# SCH_pave_2026-02-10.net
KiCad netlist of a schematic drawn in EasyEDA
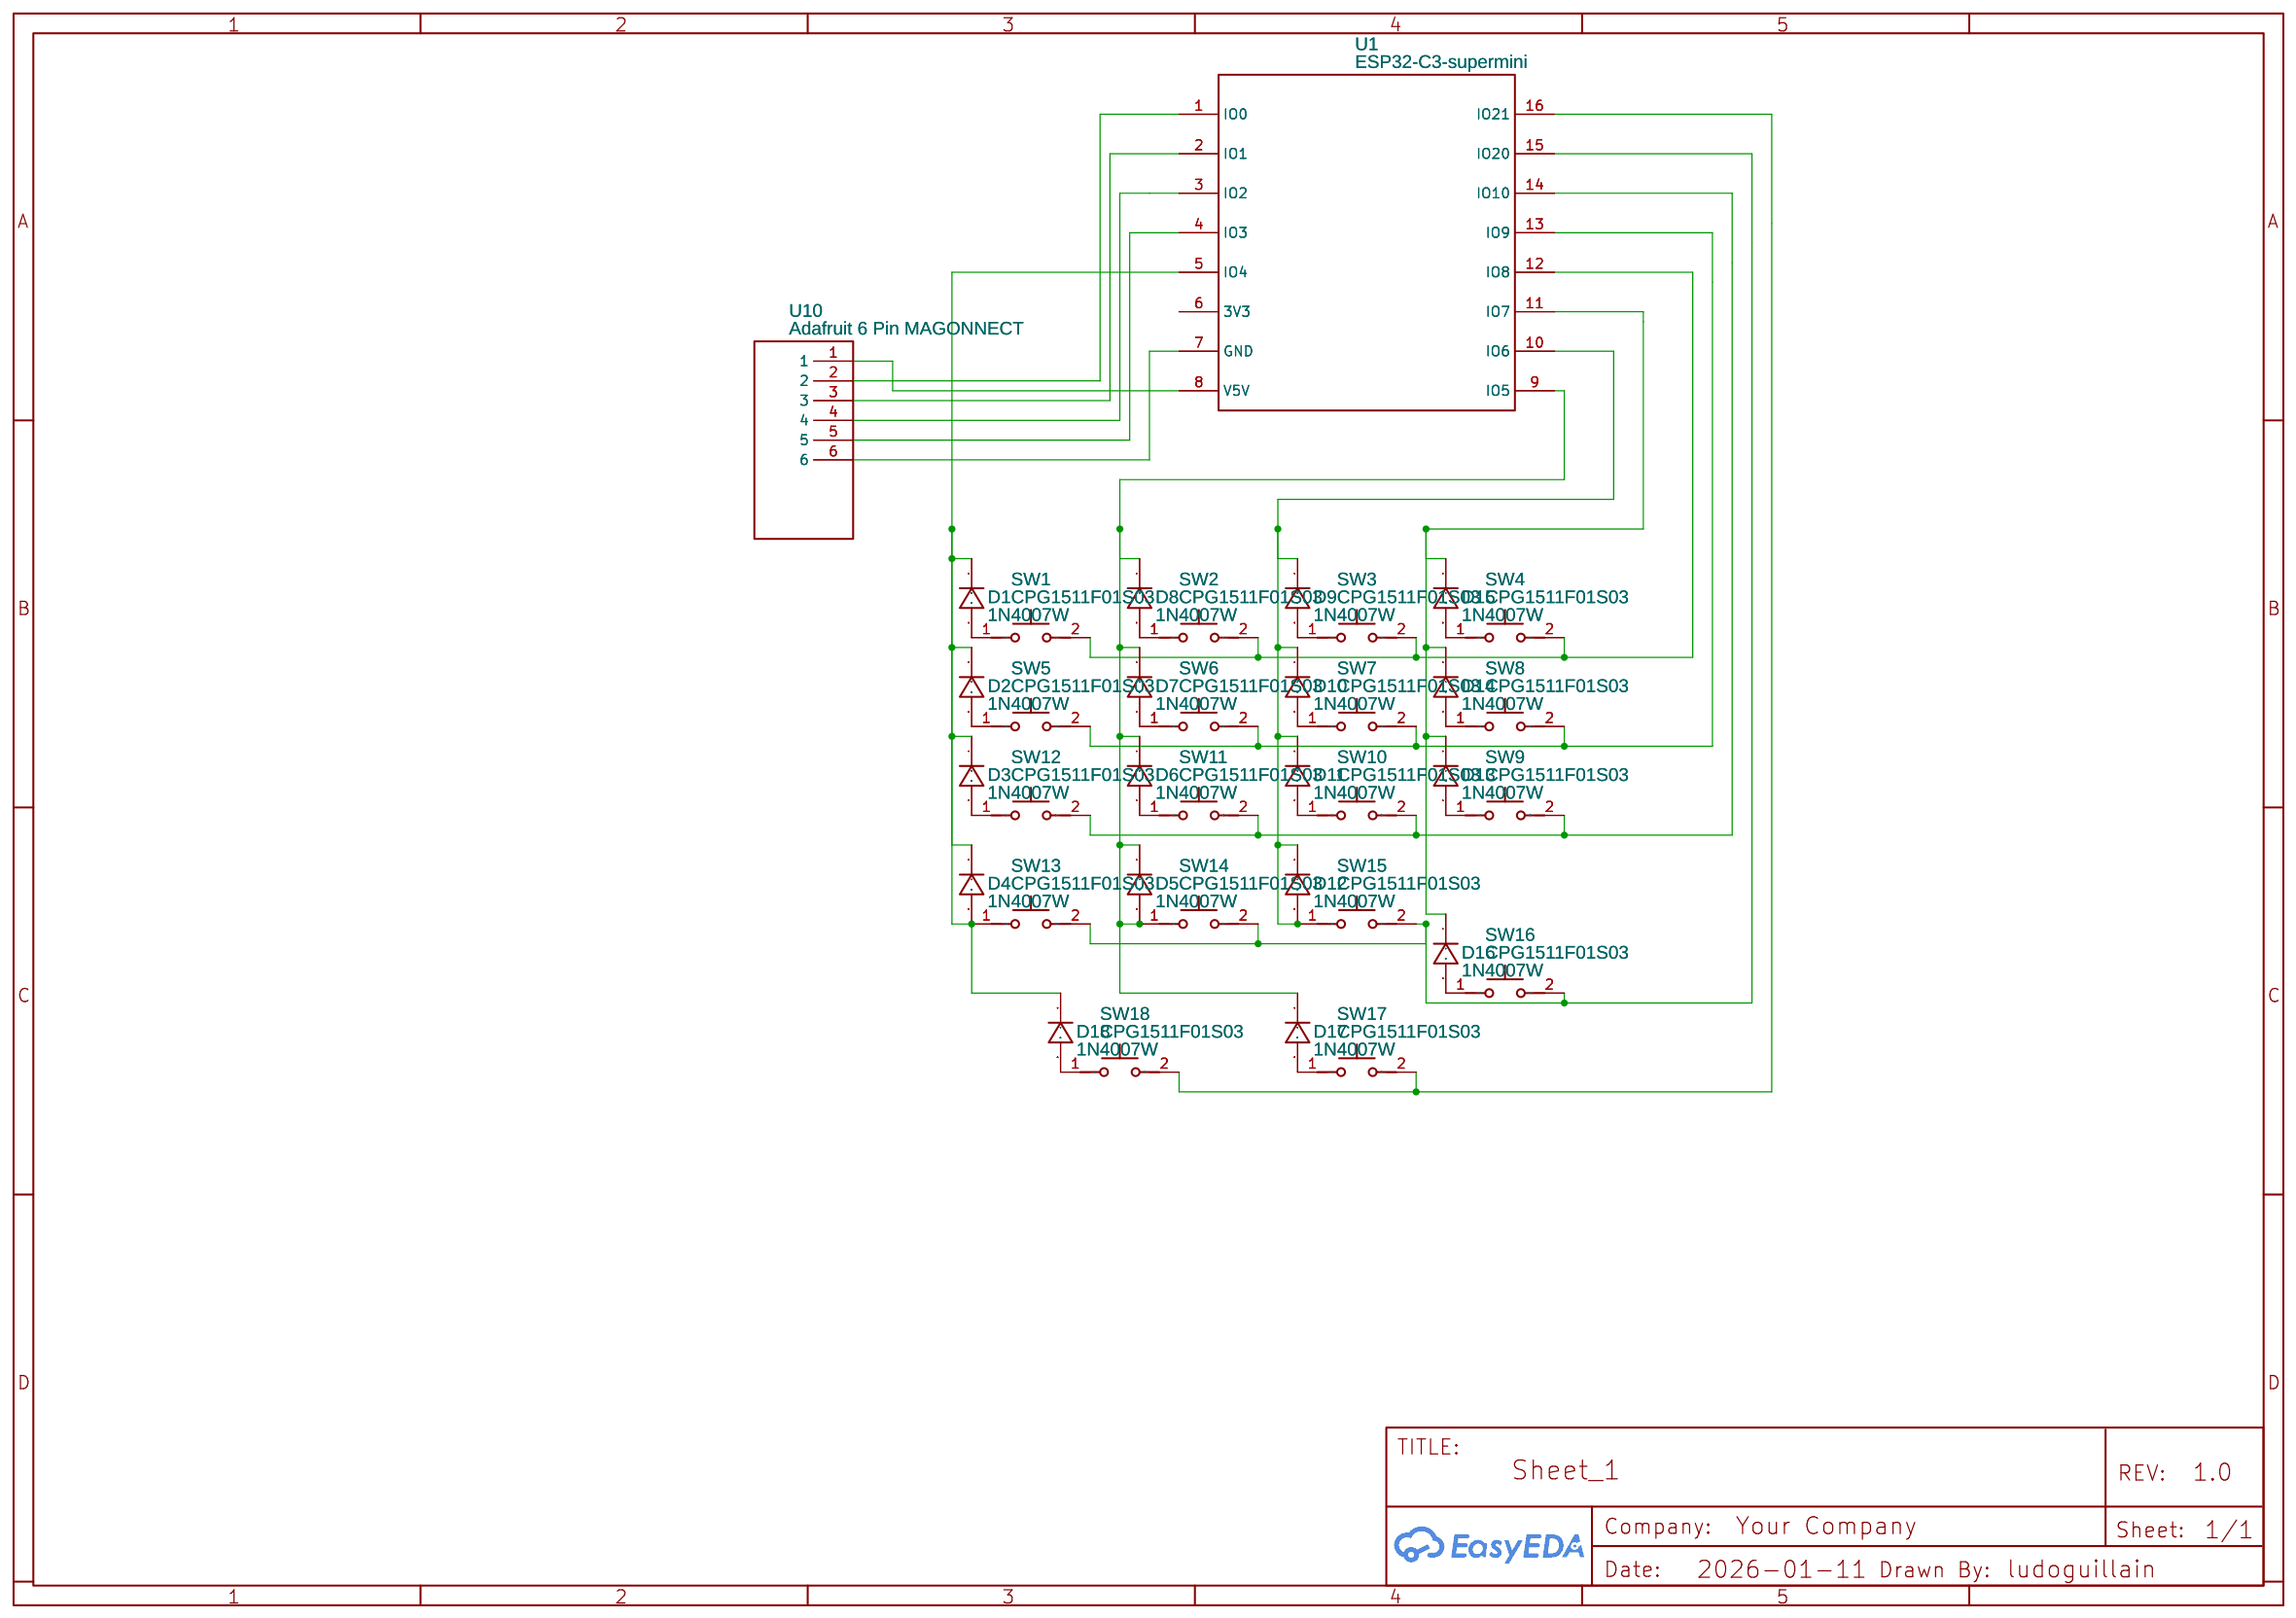
[diagram p0: schematic sheet]

(export (version "E")
  (design (tool "Eeschema 10.0.6"))
  (components
    (comp (ref "D1")
      (value "1N4007W")
      (fields (field (name "Manufacturer") "BLUE ROCKET"))
      (libsource (lib "") (part "1N4007W"))
    )
    (comp (ref "D2")
      (value "1N4007W")
      (fields (field (name "Manufacturer") "BLUE ROCKET"))
      (libsource (lib "") (part "1N4007W"))
    )
    (comp (ref "D3")
      (value "1N4007W")
      (fields (field (name "Manufacturer") "BLUE ROCKET"))
      (libsource (lib "") (part "1N4007W"))
    )
    (comp (ref "D4")
      (value "1N4007W")
      (fields (field (name "Manufacturer") "BLUE ROCKET"))
      (libsource (lib "") (part "1N4007W"))
    )
    (comp (ref "D5")
      (value "1N4007W")
      (fields (field (name "Manufacturer") "BLUE ROCKET"))
      (libsource (lib "") (part "1N4007W"))
    )
    (comp (ref "D6")
      (value "1N4007W")
      (fields (field (name "Manufacturer") "BLUE ROCKET"))
      (libsource (lib "") (part "1N4007W"))
    )
    (comp (ref "D7")
      (value "1N4007W")
      (fields (field (name "Manufacturer") "BLUE ROCKET"))
      (libsource (lib "") (part "1N4007W"))
    )
    (comp (ref "D8")
      (value "1N4007W")
      (fields (field (name "Manufacturer") "BLUE ROCKET"))
      (libsource (lib "") (part "1N4007W"))
    )
    (comp (ref "D9")
      (value "1N4007W")
      (fields (field (name "Manufacturer") "BLUE ROCKET"))
      (libsource (lib "") (part "1N4007W"))
    )
    (comp (ref "D10")
      (value "1N4007W")
      (fields (field (name "Manufacturer") "BLUE ROCKET"))
      (libsource (lib "") (part "1N4007W"))
    )
    (comp (ref "D11")
      (value "1N4007W")
      (fields (field (name "Manufacturer") "BLUE ROCKET"))
      (libsource (lib "") (part "1N4007W"))
    )
    (comp (ref "D12")
      (value "1N4007W")
      (fields (field (name "Manufacturer") "BLUE ROCKET"))
      (libsource (lib "") (part "1N4007W"))
    )
    (comp (ref "D13")
      (value "1N4007W")
      (fields (field (name "Manufacturer") "BLUE ROCKET"))
      (libsource (lib "") (part "1N4007W"))
    )
    (comp (ref "D14")
      (value "1N4007W")
      (fields (field (name "Manufacturer") "BLUE ROCKET"))
      (libsource (lib "") (part "1N4007W"))
    )
    (comp (ref "D15")
      (value "1N4007W")
      (fields (field (name "Manufacturer") "BLUE ROCKET"))
      (libsource (lib "") (part "1N4007W"))
    )
    (comp (ref "D16")
      (value "1N4007W")
      (fields (field (name "Manufacturer") "BLUE ROCKET"))
      (libsource (lib "") (part "1N4007W"))
    )
    (comp (ref "D17")
      (value "1N4007W")
      (fields (field (name "Manufacturer") "BLUE ROCKET"))
      (libsource (lib "") (part "1N4007W"))
    )
    (comp (ref "D18")
      (value "1N4007W")
      (fields (field (name "Manufacturer") "BLUE ROCKET"))
      (libsource (lib "") (part "1N4007W"))
    )
    (comp (ref "SW1")
      (value "CPG1511F01S03")
      (fields (field (name "Manufacturer") "Kailh(凯华)"))
      (libsource (lib "") (part "CPG1511F01S03"))
    )
    (comp (ref "SW2")
      (value "CPG1511F01S03")
      (fields (field (name "Manufacturer") "Kailh(凯华)"))
      (libsource (lib "") (part "CPG1511F01S03"))
    )
    (comp (ref "SW3")
      (value "CPG1511F01S03")
      (fields (field (name "Manufacturer") "Kailh(凯华)"))
      (libsource (lib "") (part "CPG1511F01S03"))
    )
    (comp (ref "SW4")
      (value "CPG1511F01S03")
      (fields (field (name "Manufacturer") "Kailh(凯华)"))
      (libsource (lib "") (part "CPG1511F01S03"))
    )
    (comp (ref "SW5")
      (value "CPG1511F01S03")
      (fields (field (name "Manufacturer") "Kailh(凯华)"))
      (libsource (lib "") (part "CPG1511F01S03"))
    )
    (comp (ref "SW6")
      (value "CPG1511F01S03")
      (fields (field (name "Manufacturer") "Kailh(凯华)"))
      (libsource (lib "") (part "CPG1511F01S03"))
    )
    (comp (ref "SW7")
      (value "CPG1511F01S03")
      (fields (field (name "Manufacturer") "Kailh(凯华)"))
      (libsource (lib "") (part "CPG1511F01S03"))
    )
    (comp (ref "SW8")
      (value "CPG1511F01S03")
      (fields (field (name "Manufacturer") "Kailh(凯华)"))
      (libsource (lib "") (part "CPG1511F01S03"))
    )
    (comp (ref "SW9")
      (value "CPG1511F01S03")
      (fields (field (name "Manufacturer") "Kailh(凯华)"))
      (libsource (lib "") (part "CPG1511F01S03"))
    )
    (comp (ref "SW10")
      (value "CPG1511F01S03")
      (fields (field (name "Manufacturer") "Kailh(凯华)"))
      (libsource (lib "") (part "CPG1511F01S03"))
    )
    (comp (ref "SW11")
      (value "CPG1511F01S03")
      (fields (field (name "Manufacturer") "Kailh(凯华)"))
      (libsource (lib "") (part "CPG1511F01S03"))
    )
    (comp (ref "SW12")
      (value "CPG1511F01S03")
      (fields (field (name "Manufacturer") "Kailh(凯华)"))
      (libsource (lib "") (part "CPG1511F01S03"))
    )
    (comp (ref "SW13")
      (value "CPG1511F01S03")
      (fields (field (name "Manufacturer") "Kailh(凯华)"))
      (libsource (lib "") (part "CPG1511F01S03"))
    )
    (comp (ref "SW14")
      (value "CPG1511F01S03")
      (fields (field (name "Manufacturer") "Kailh(凯华)"))
      (libsource (lib "") (part "CPG1511F01S03"))
    )
    (comp (ref "SW15")
      (value "CPG1511F01S03")
      (fields (field (name "Manufacturer") "Kailh(凯华)"))
      (libsource (lib "") (part "CPG1511F01S03"))
    )
    (comp (ref "SW16")
      (value "CPG1511F01S03")
      (fields (field (name "Manufacturer") "Kailh(凯华)"))
      (libsource (lib "") (part "CPG1511F01S03"))
    )
    (comp (ref "SW17")
      (value "CPG1511F01S03")
      (fields (field (name "Manufacturer") "Kailh(凯华)"))
      (libsource (lib "") (part "CPG1511F01S03"))
    )
    (comp (ref "SW18")
      (value "CPG1511F01S03")
      (fields (field (name "Manufacturer") "Kailh(凯华)"))
      (libsource (lib "") (part "CPG1511F01S03"))
    )
    (comp (ref "U1") (value "ESP32-C3-supermini") (libsource (lib "") (part "ESP32-C3-supermini")))
    (comp (ref "U10")
      (value "Adafruit 6 Pin MAGONNECT")
      (libsource (lib "") (part "Adafruit 6 Pin MAGONNECT"))
    )
  )
  (nets
    (net (code "1") (name "Net-(D1-Pad2)") (class "Default")
      (node (ref "D1") (pin "2") (pinfunction "2_2") (pintype "unspecified"))
      (node (ref "SW1") (pin "1") (pinfunction "1_1") (pintype "unspecified"))
    )
    (net (code "2") (name "Net-(D2-Pad2)") (class "Default")
      (node (ref "D2") (pin "2") (pinfunction "2_2") (pintype "unspecified"))
      (node (ref "SW5") (pin "1") (pinfunction "1_1") (pintype "unspecified"))
    )
    (net (code "3") (name "Net-(D3-Pad2)") (class "Default")
      (node (ref "D3") (pin "2") (pinfunction "2_2") (pintype "unspecified"))
      (node (ref "SW12") (pin "1") (pinfunction "1_1") (pintype "unspecified"))
    )
    (net (code "4") (name "Net-(D6-Pad2)") (class "Default")
      (node (ref "D6") (pin "2") (pinfunction "2_2") (pintype "unspecified"))
      (node (ref "SW11") (pin "1") (pinfunction "1_1") (pintype "unspecified"))
    )
    (net (code "5") (name "Net-(D7-Pad2)") (class "Default")
      (node (ref "D7") (pin "2") (pinfunction "2_2") (pintype "unspecified"))
      (node (ref "SW6") (pin "1") (pinfunction "1_1") (pintype "unspecified"))
    )
    (net (code "6") (name "Net-(D8-Pad2)") (class "Default")
      (node (ref "D8") (pin "2") (pinfunction "2_2") (pintype "unspecified"))
      (node (ref "SW2") (pin "1") (pinfunction "1_1") (pintype "unspecified"))
    )
    (net (code "7") (name "Net-(D9-Pad2)") (class "Default")
      (node (ref "D9") (pin "2") (pinfunction "2_2") (pintype "unspecified"))
      (node (ref "SW3") (pin "1") (pinfunction "1_1") (pintype "unspecified"))
    )
    (net (code "8") (name "Net-(D10-Pad2)") (class "Default")
      (node (ref "D10") (pin "2") (pinfunction "2_2") (pintype "unspecified"))
      (node (ref "SW7") (pin "1") (pinfunction "1_1") (pintype "unspecified"))
    )
    (net (code "9") (name "Net-(D11-Pad2)") (class "Default")
      (node (ref "D11") (pin "2") (pinfunction "2_2") (pintype "unspecified"))
      (node (ref "SW10") (pin "1") (pinfunction "1_1") (pintype "unspecified"))
    )
    (net (code "10") (name "Net-(D13-Pad2)") (class "Default")
      (node (ref "D13") (pin "2") (pinfunction "2_2") (pintype "unspecified"))
      (node (ref "SW9") (pin "1") (pinfunction "1_1") (pintype "unspecified"))
    )
    (net (code "11") (name "Net-(D14-Pad2)") (class "Default")
      (node (ref "D14") (pin "2") (pinfunction "2_2") (pintype "unspecified"))
      (node (ref "SW8") (pin "1") (pinfunction "1_1") (pintype "unspecified"))
    )
    (net (code "12") (name "Net-(D15-Pad2)") (class "Default")
      (node (ref "D15") (pin "2") (pinfunction "2_2") (pintype "unspecified"))
      (node (ref "SW4") (pin "1") (pinfunction "1_1") (pintype "unspecified"))
    )
    (net (code "13") (name "Net-(D16-Pad2)") (class "Default")
      (node (ref "D16") (pin "2") (pinfunction "2_2") (pintype "unspecified"))
      (node (ref "SW16") (pin "1") (pinfunction "1_1") (pintype "unspecified"))
    )
    (net (code "14") (name "Net-(D17-Pad2)") (class "Default")
      (node (ref "D17") (pin "2") (pinfunction "2_2") (pintype "unspecified"))
      (node (ref "SW17") (pin "1") (pinfunction "1_1") (pintype "unspecified"))
    )
    (net (code "15") (name "Net-(D18-Pad2)") (class "Default")
      (node (ref "D18") (pin "2") (pinfunction "2_2") (pintype "unspecified"))
      (node (ref "SW18") (pin "1") (pinfunction "1_1") (pintype "unspecified"))
    )
    (net (code "16") (name "Net-(U1-GND)") (class "Default")
      (node (ref "U1") (pin "7") (pinfunction "GND_7") (pintype "unspecified"))
      (node (ref "U10") (pin "6") (pinfunction "6_6") (pintype "unspecified"))
    )
    (net (code "17") (name "Net-(U1-IO0)") (class "Default")
      (node (ref "U1") (pin "1") (pinfunction "IO0_1") (pintype "unspecified"))
      (node (ref "U10") (pin "2") (pinfunction "2_2") (pintype "unspecified"))
    )
    (net (code "18") (name "Net-(U1-IO1)") (class "Default")
      (node (ref "U1") (pin "2") (pinfunction "IO1_2") (pintype "unspecified"))
      (node (ref "U10") (pin "3") (pinfunction "3_3") (pintype "unspecified"))
    )
    (net (code "19") (name "Net-(U1-IO2)") (class "Default")
      (node (ref "U1") (pin "3") (pinfunction "IO2_3") (pintype "unspecified"))
      (node (ref "U10") (pin "4") (pinfunction "4_4") (pintype "unspecified"))
    )
    (net (code "20") (name "Net-(U1-IO3)") (class "Default")
      (node (ref "U1") (pin "4") (pinfunction "IO3_4") (pintype "unspecified"))
      (node (ref "U10") (pin "5") (pinfunction "5_5") (pintype "unspecified"))
    )
    (net (code "21") (name "Net-(U1-IO4)") (class "Default")
      (node (ref "D1") (pin "1") (pinfunction "1_1") (pintype "unspecified"))
      (node (ref "D18") (pin "1") (pinfunction "1_1") (pintype "unspecified"))
      (node (ref "D2") (pin "1") (pinfunction "1_1") (pintype "unspecified"))
      (node (ref "D3") (pin "1") (pinfunction "1_1") (pintype "unspecified"))
      (node (ref "D4") (pin "1") (pinfunction "1_1") (pintype "unspecified"))
      (node (ref "D4") (pin "2") (pinfunction "2_2") (pintype "unspecified"))
      (node (ref "SW13") (pin "1") (pinfunction "1_1") (pintype "unspecified"))
      (node (ref "U1") (pin "5") (pinfunction "IO4_5") (pintype "unspecified"))
    )
    (net (code "22") (name "Net-(U1-IO5)") (class "Default")
      (node (ref "D17") (pin "1") (pinfunction "1_1") (pintype "unspecified"))
      (node (ref "D5") (pin "1") (pinfunction "1_1") (pintype "unspecified"))
      (node (ref "D5") (pin "2") (pinfunction "2_2") (pintype "unspecified"))
      (node (ref "D6") (pin "1") (pinfunction "1_1") (pintype "unspecified"))
      (node (ref "D7") (pin "1") (pinfunction "1_1") (pintype "unspecified"))
      (node (ref "D8") (pin "1") (pinfunction "1_1") (pintype "unspecified"))
      (node (ref "SW14") (pin "1") (pinfunction "1_1") (pintype "unspecified"))
      (node (ref "U1") (pin "9") (pinfunction "IO5_9") (pintype "unspecified"))
    )
    (net (code "23") (name "Net-(U1-IO6)") (class "Default")
      (node (ref "D10") (pin "1") (pinfunction "1_1") (pintype "unspecified"))
      (node (ref "D11") (pin "1") (pinfunction "1_1") (pintype "unspecified"))
      (node (ref "D12") (pin "1") (pinfunction "1_1") (pintype "unspecified"))
      (node (ref "D12") (pin "2") (pinfunction "2_2") (pintype "unspecified"))
      (node (ref "D9") (pin "1") (pinfunction "1_1") (pintype "unspecified"))
      (node (ref "SW15") (pin "1") (pinfunction "1_1") (pintype "unspecified"))
      (node (ref "U1") (pin "10") (pinfunction "IO6_10") (pintype "unspecified"))
    )
    (net (code "24") (name "Net-(U1-IO7)") (class "Default")
      (node (ref "D13") (pin "1") (pinfunction "1_1") (pintype "unspecified"))
      (node (ref "D14") (pin "1") (pinfunction "1_1") (pintype "unspecified"))
      (node (ref "D15") (pin "1") (pinfunction "1_1") (pintype "unspecified"))
      (node (ref "D16") (pin "1") (pinfunction "1_1") (pintype "unspecified"))
      (node (ref "U1") (pin "11") (pinfunction "IO7_11") (pintype "unspecified"))
    )
    (net (code "25") (name "Net-(U1-IO8)") (class "Default")
      (node (ref "SW1") (pin "2") (pinfunction "2_2") (pintype "unspecified"))
      (node (ref "SW2") (pin "2") (pinfunction "2_2") (pintype "unspecified"))
      (node (ref "SW3") (pin "2") (pinfunction "2_2") (pintype "unspecified"))
      (node (ref "SW4") (pin "2") (pinfunction "2_2") (pintype "unspecified"))
      (node (ref "U1") (pin "12") (pinfunction "IO8_12") (pintype "unspecified"))
    )
    (net (code "26") (name "Net-(U1-IO9)") (class "Default")
      (node (ref "SW5") (pin "2") (pinfunction "2_2") (pintype "unspecified"))
      (node (ref "SW6") (pin "2") (pinfunction "2_2") (pintype "unspecified"))
      (node (ref "SW7") (pin "2") (pinfunction "2_2") (pintype "unspecified"))
      (node (ref "SW8") (pin "2") (pinfunction "2_2") (pintype "unspecified"))
      (node (ref "U1") (pin "13") (pinfunction "IO9_13") (pintype "unspecified"))
    )
    (net (code "27") (name "Net-(U1-IO10)") (class "Default")
      (node (ref "SW10") (pin "2") (pinfunction "2_2") (pintype "unspecified"))
      (node (ref "SW11") (pin "2") (pinfunction "2_2") (pintype "unspecified"))
      (node (ref "SW12") (pin "2") (pinfunction "2_2") (pintype "unspecified"))
      (node (ref "SW9") (pin "2") (pinfunction "2_2") (pintype "unspecified"))
      (node (ref "U1") (pin "14") (pinfunction "IO10_14") (pintype "unspecified"))
    )
    (net (code "28") (name "Net-(U1-IO20)") (class "Default")
      (node (ref "SW13") (pin "2") (pinfunction "2_2") (pintype "unspecified"))
      (node (ref "SW14") (pin "2") (pinfunction "2_2") (pintype "unspecified"))
      (node (ref "SW15") (pin "2") (pinfunction "2_2") (pintype "unspecified"))
      (node (ref "SW16") (pin "2") (pinfunction "2_2") (pintype "unspecified"))
      (node (ref "U1") (pin "15") (pinfunction "IO20_15") (pintype "unspecified"))
    )
    (net (code "29") (name "Net-(U1-IO21)") (class "Default")
      (node (ref "SW17") (pin "2") (pinfunction "2_2") (pintype "unspecified"))
      (node (ref "SW18") (pin "2") (pinfunction "2_2") (pintype "unspecified"))
      (node (ref "U1") (pin "16") (pinfunction "IO21_16") (pintype "unspecified"))
    )
    (net (code "30") (name "Net-(U1-V5V)") (class "Default")
      (node (ref "U1") (pin "8") (pinfunction "V5V_8") (pintype "unspecified"))
      (node (ref "U10") (pin "1") (pinfunction "1_1") (pintype "unspecified"))
    )
    (net (code "31") (name "unconnected-(U1-3V3-Pad6)") (class "Default")
      (node (ref "U1") (pin "6") (pinfunction "3V3_6") (pintype "unspecified"))
    )
  )
)
